# test.net
KiCad netlist of a schematic drawn in EAGLE
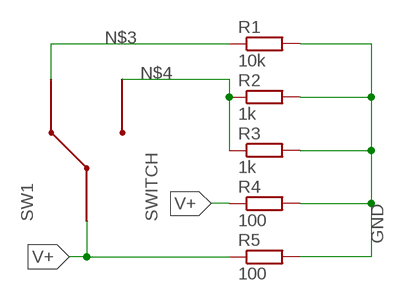
[diagram p0: schematic, sheet 1]

(export (version "E")
  (design (tool "Eeschema 10.0.6"))
  (components
    (comp (ref "R1")
      (value "10k")
      (footprint "eagle-import:R3216W")
      (libsource (lib "eagle-import") (part "R-EU_R3216W"))
    )
    (comp (ref "R2")
      (value "1k")
      (footprint "eagle-import:R3216W")
      (libsource (lib "eagle-import") (part "R-EU_R3216W"))
    )
    (comp (ref "R3")
      (value "1k")
      (footprint "eagle-import:R3216W")
      (libsource (lib "eagle-import") (part "R-EU_R3216W"))
    )
    (comp (ref "R4")
      (value "100")
      (footprint "eagle-import:R3216W")
      (libsource (lib "eagle-import") (part "R-EU_R3216W"))
    )
    (comp (ref "R5")
      (value "100")
      (footprint "eagle-import:R3216W")
      (libsource (lib "eagle-import") (part "R-EU_R3216W"))
    )
    (comp (ref "SW1")
      (value "SWITCH")
      (footprint "eagle-import:SW3")
      (libsource (lib "eagle-import") (part "SWITCH"))
    )
  )
  (nets
    (net (code "1") (name "/GND") (class "Default")
      (node (ref "R1") (pin "2") (pinfunction "2_2") (pintype "passive"))
      (node (ref "R2") (pin "2") (pinfunction "2_2") (pintype "passive"))
      (node (ref "R3") (pin "2") (pinfunction "2_2") (pintype "passive"))
      (node (ref "R4") (pin "2") (pinfunction "2_2") (pintype "passive"))
      (node (ref "R5") (pin "2") (pinfunction "2_2") (pintype "passive"))
    )
    (net (code "2") (name "/N$3") (class "Default")
      (node (ref "R1") (pin "1") (pinfunction "1_1") (pintype "passive"))
      (node (ref "SW1") (pin "P1") (pinfunction "P1_P1") (pintype "passive"))
    )
    (net (code "3") (name "/N$4") (class "Default")
      (node (ref "R2") (pin "1") (pinfunction "1_1") (pintype "passive"))
      (node (ref "R3") (pin "1") (pinfunction "1_1") (pintype "passive"))
      (node (ref "SW1") (pin "P3") (pinfunction "P3_P3") (pintype "passive"))
    )
    (net (code "4") (name "V+") (class "Default")
      (node (ref "R4") (pin "1") (pinfunction "1_1") (pintype "passive"))
      (node (ref "R5") (pin "1") (pinfunction "1_1") (pintype "passive"))
      (node (ref "SW1") (pin "P2") (pinfunction "P2_P2") (pintype "passive"))
    )
  )
)
